# LED_Pannel.net
KiCad netlist of a schematic drawn in EAGLE
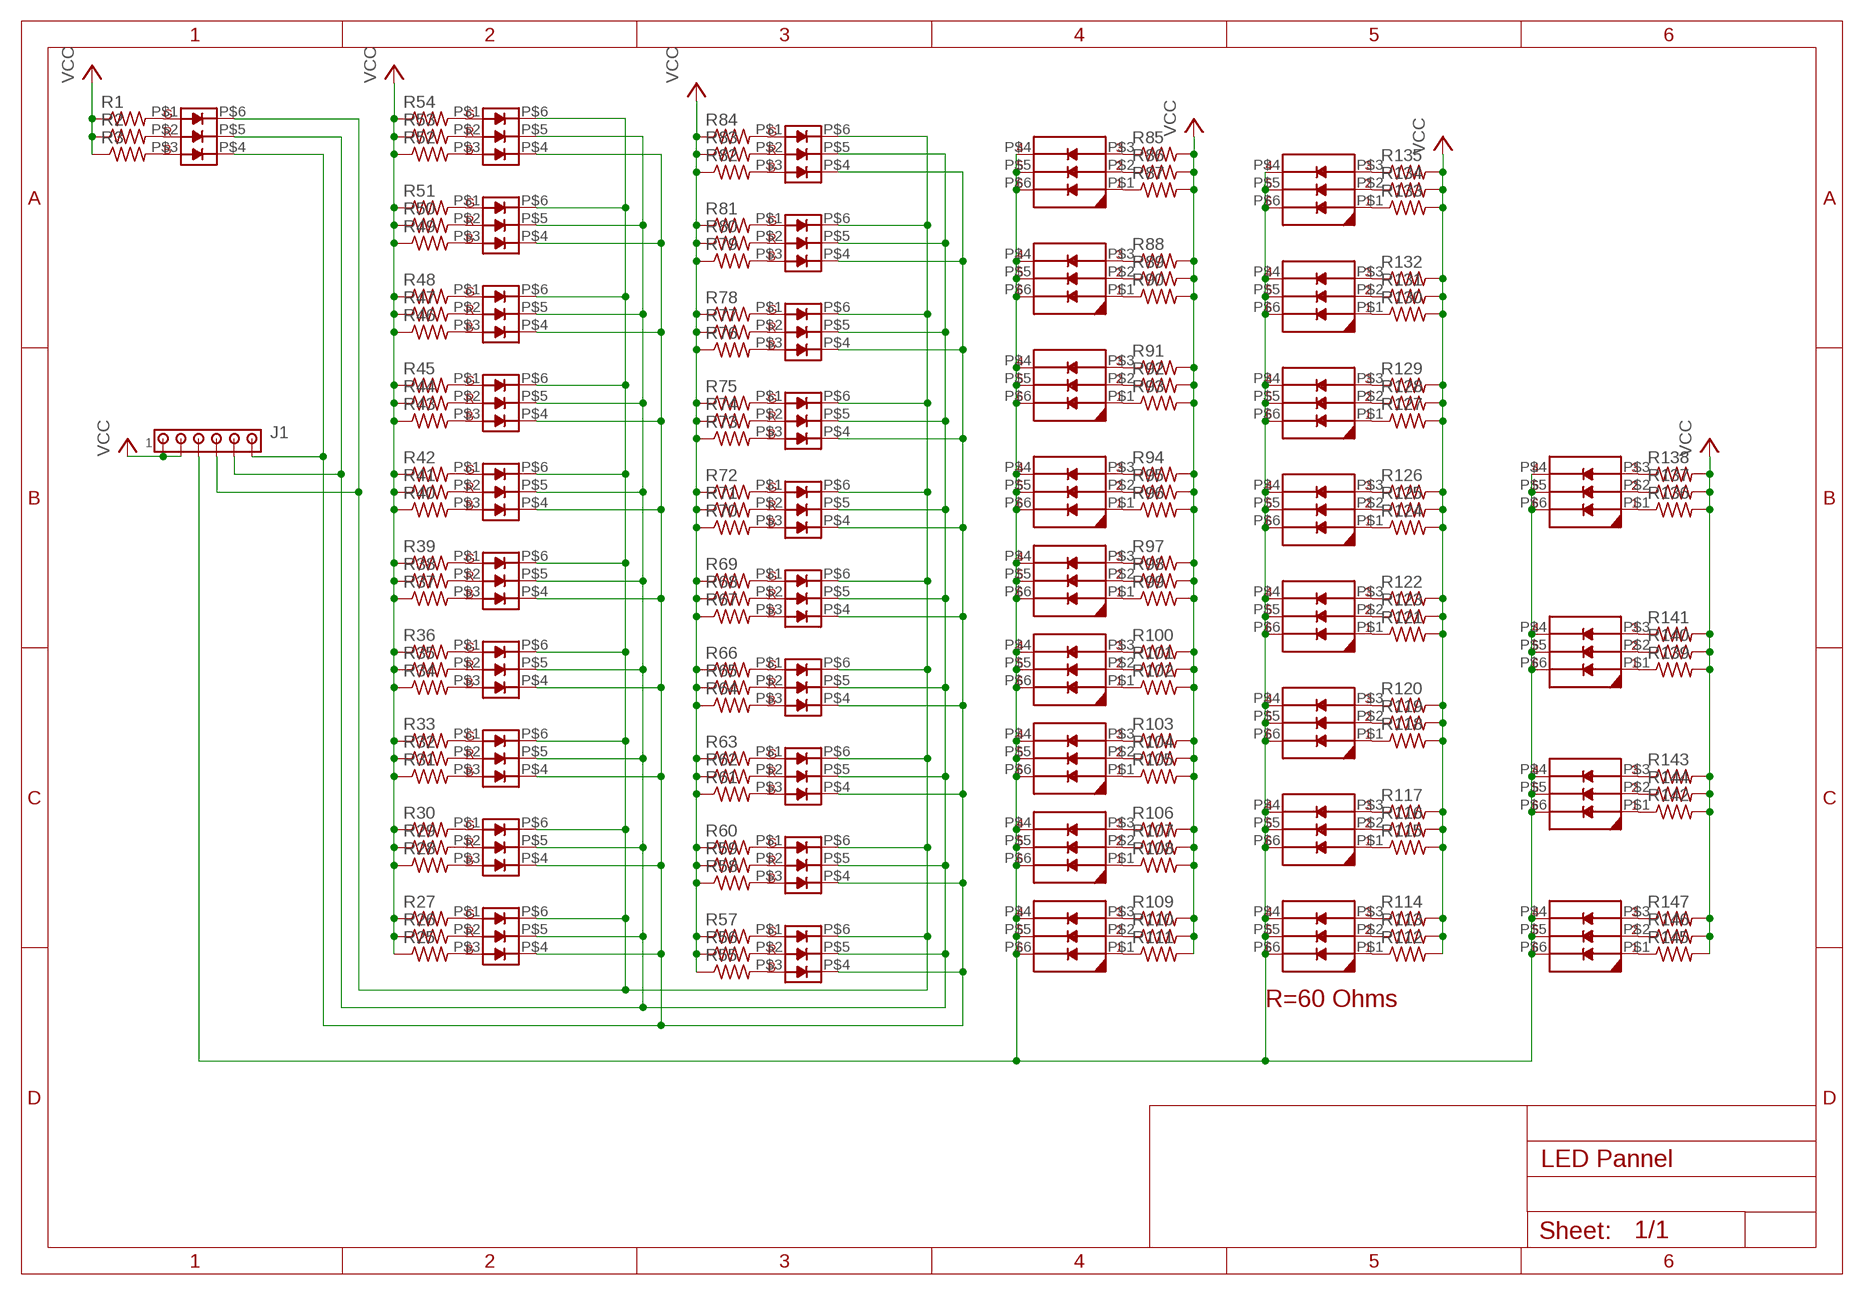
[diagram p0: schematic, sheet 1]

(export (version "E")
  (design (tool "Eeschema 10.0.6"))
  (components
    (comp (ref "J1")
      (value "MTA06-156")
      (footprint "eagle-import:1X6MTA")
      (libsource (lib "eagle-import") (part "MTA06-156"))
    )
    (comp (ref "R1")
      (value "R-US_R0603")
      (footprint "eagle-import:R0603")
      (libsource (lib "eagle-import") (part "R-US_R0603"))
    )
    (comp (ref "R2")
      (value "R-US_R0603")
      (footprint "eagle-import:R0603")
      (libsource (lib "eagle-import") (part "R-US_R0603"))
    )
    (comp (ref "R3")
      (value "R-US_R0603")
      (footprint "eagle-import:R0603")
      (libsource (lib "eagle-import") (part "R-US_R0603"))
    )
    (comp (ref "R25")
      (value "R-US_R0603")
      (footprint "eagle-import:R0603")
      (libsource (lib "eagle-import") (part "R-US_R0603"))
    )
    (comp (ref "R26")
      (value "R-US_R0603")
      (footprint "eagle-import:R0603")
      (libsource (lib "eagle-import") (part "R-US_R0603"))
    )
    (comp (ref "R27")
      (value "R-US_R0603")
      (footprint "eagle-import:R0603")
      (libsource (lib "eagle-import") (part "R-US_R0603"))
    )
    (comp (ref "R28")
      (value "R-US_R0603")
      (footprint "eagle-import:R0603")
      (libsource (lib "eagle-import") (part "R-US_R0603"))
    )
    (comp (ref "R29")
      (value "R-US_R0603")
      (footprint "eagle-import:R0603")
      (libsource (lib "eagle-import") (part "R-US_R0603"))
    )
    (comp (ref "R30")
      (value "R-US_R0603")
      (footprint "eagle-import:R0603")
      (libsource (lib "eagle-import") (part "R-US_R0603"))
    )
    (comp (ref "R31")
      (value "R-US_R0603")
      (footprint "eagle-import:R0603")
      (libsource (lib "eagle-import") (part "R-US_R0603"))
    )
    (comp (ref "R32")
      (value "R-US_R0603")
      (footprint "eagle-import:R0603")
      (libsource (lib "eagle-import") (part "R-US_R0603"))
    )
    (comp (ref "R33")
      (value "R-US_R0603")
      (footprint "eagle-import:R0603")
      (libsource (lib "eagle-import") (part "R-US_R0603"))
    )
    (comp (ref "R34")
      (value "R-US_R0603")
      (footprint "eagle-import:R0603")
      (libsource (lib "eagle-import") (part "R-US_R0603"))
    )
    (comp (ref "R35")
      (value "R-US_R0603")
      (footprint "eagle-import:R0603")
      (libsource (lib "eagle-import") (part "R-US_R0603"))
    )
    (comp (ref "R36")
      (value "R-US_R0603")
      (footprint "eagle-import:R0603")
      (libsource (lib "eagle-import") (part "R-US_R0603"))
    )
    (comp (ref "R37")
      (value "R-US_R0603")
      (footprint "eagle-import:R0603")
      (libsource (lib "eagle-import") (part "R-US_R0603"))
    )
    (comp (ref "R38")
      (value "R-US_R0603")
      (footprint "eagle-import:R0603")
      (libsource (lib "eagle-import") (part "R-US_R0603"))
    )
    (comp (ref "R39")
      (value "R-US_R0603")
      (footprint "eagle-import:R0603")
      (libsource (lib "eagle-import") (part "R-US_R0603"))
    )
    (comp (ref "R40")
      (value "R-US_R0603")
      (footprint "eagle-import:R0603")
      (libsource (lib "eagle-import") (part "R-US_R0603"))
    )
    (comp (ref "R41")
      (value "R-US_R0603")
      (footprint "eagle-import:R0603")
      (libsource (lib "eagle-import") (part "R-US_R0603"))
    )
    (comp (ref "R42")
      (value "R-US_R0603")
      (footprint "eagle-import:R0603")
      (libsource (lib "eagle-import") (part "R-US_R0603"))
    )
    (comp (ref "R43")
      (value "R-US_R0603")
      (footprint "eagle-import:R0603")
      (libsource (lib "eagle-import") (part "R-US_R0603"))
    )
    (comp (ref "R44")
      (value "R-US_R0603")
      (footprint "eagle-import:R0603")
      (libsource (lib "eagle-import") (part "R-US_R0603"))
    )
    (comp (ref "R45")
      (value "R-US_R0603")
      (footprint "eagle-import:R0603")
      (libsource (lib "eagle-import") (part "R-US_R0603"))
    )
    (comp (ref "R46")
      (value "R-US_R0603")
      (footprint "eagle-import:R0603")
      (libsource (lib "eagle-import") (part "R-US_R0603"))
    )
    (comp (ref "R47")
      (value "R-US_R0603")
      (footprint "eagle-import:R0603")
      (libsource (lib "eagle-import") (part "R-US_R0603"))
    )
    (comp (ref "R48")
      (value "R-US_R0603")
      (footprint "eagle-import:R0603")
      (libsource (lib "eagle-import") (part "R-US_R0603"))
    )
    (comp (ref "R49")
      (value "R-US_R0603")
      (footprint "eagle-import:R0603")
      (libsource (lib "eagle-import") (part "R-US_R0603"))
    )
    (comp (ref "R50")
      (value "R-US_R0603")
      (footprint "eagle-import:R0603")
      (libsource (lib "eagle-import") (part "R-US_R0603"))
    )
    (comp (ref "R51")
      (value "R-US_R0603")
      (footprint "eagle-import:R0603")
      (libsource (lib "eagle-import") (part "R-US_R0603"))
    )
    (comp (ref "R52")
      (value "R-US_R0603")
      (footprint "eagle-import:R0603")
      (libsource (lib "eagle-import") (part "R-US_R0603"))
    )
    (comp (ref "R53")
      (value "R-US_R0603")
      (footprint "eagle-import:R0603")
      (libsource (lib "eagle-import") (part "R-US_R0603"))
    )
    (comp (ref "R54")
      (value "R-US_R0603")
      (footprint "eagle-import:R0603")
      (libsource (lib "eagle-import") (part "R-US_R0603"))
    )
    (comp (ref "R55")
      (value "R-US_R0603")
      (footprint "eagle-import:R0603")
      (libsource (lib "eagle-import") (part "R-US_R0603"))
    )
    (comp (ref "R56")
      (value "R-US_R0603")
      (footprint "eagle-import:R0603")
      (libsource (lib "eagle-import") (part "R-US_R0603"))
    )
    (comp (ref "R57")
      (value "R-US_R0603")
      (footprint "eagle-import:R0603")
      (libsource (lib "eagle-import") (part "R-US_R0603"))
    )
    (comp (ref "R58")
      (value "R-US_R0603")
      (footprint "eagle-import:R0603")
      (libsource (lib "eagle-import") (part "R-US_R0603"))
    )
    (comp (ref "R59")
      (value "R-US_R0603")
      (footprint "eagle-import:R0603")
      (libsource (lib "eagle-import") (part "R-US_R0603"))
    )
    (comp (ref "R60")
      (value "R-US_R0603")
      (footprint "eagle-import:R0603")
      (libsource (lib "eagle-import") (part "R-US_R0603"))
    )
    (comp (ref "R61")
      (value "R-US_R0603")
      (footprint "eagle-import:R0603")
      (libsource (lib "eagle-import") (part "R-US_R0603"))
    )
    (comp (ref "R62")
      (value "R-US_R0603")
      (footprint "eagle-import:R0603")
      (libsource (lib "eagle-import") (part "R-US_R0603"))
    )
    (comp (ref "R63")
      (value "R-US_R0603")
      (footprint "eagle-import:R0603")
      (libsource (lib "eagle-import") (part "R-US_R0603"))
    )
    (comp (ref "R64")
      (value "R-US_R0603")
      (footprint "eagle-import:R0603")
      (libsource (lib "eagle-import") (part "R-US_R0603"))
    )
    (comp (ref "R65")
      (value "R-US_R0603")
      (footprint "eagle-import:R0603")
      (libsource (lib "eagle-import") (part "R-US_R0603"))
    )
    (comp (ref "R66")
      (value "R-US_R0603")
      (footprint "eagle-import:R0603")
      (libsource (lib "eagle-import") (part "R-US_R0603"))
    )
    (comp (ref "R67")
      (value "R-US_R0603")
      (footprint "eagle-import:R0603")
      (libsource (lib "eagle-import") (part "R-US_R0603"))
    )
    (comp (ref "R68")
      (value "R-US_R0603")
      (footprint "eagle-import:R0603")
      (libsource (lib "eagle-import") (part "R-US_R0603"))
    )
    (comp (ref "R69")
      (value "R-US_R0603")
      (footprint "eagle-import:R0603")
      (libsource (lib "eagle-import") (part "R-US_R0603"))
    )
    (comp (ref "R70")
      (value "R-US_R0603")
      (footprint "eagle-import:R0603")
      (libsource (lib "eagle-import") (part "R-US_R0603"))
    )
    (comp (ref "R71")
      (value "R-US_R0603")
      (footprint "eagle-import:R0603")
      (libsource (lib "eagle-import") (part "R-US_R0603"))
    )
    (comp (ref "R72")
      (value "R-US_R0603")
      (footprint "eagle-import:R0603")
      (libsource (lib "eagle-import") (part "R-US_R0603"))
    )
    (comp (ref "R73")
      (value "R-US_R0603")
      (footprint "eagle-import:R0603")
      (libsource (lib "eagle-import") (part "R-US_R0603"))
    )
    (comp (ref "R74")
      (value "R-US_R0603")
      (footprint "eagle-import:R0603")
      (libsource (lib "eagle-import") (part "R-US_R0603"))
    )
    (comp (ref "R75")
      (value "R-US_R0603")
      (footprint "eagle-import:R0603")
      (libsource (lib "eagle-import") (part "R-US_R0603"))
    )
    (comp (ref "R76")
      (value "R-US_R0603")
      (footprint "eagle-import:R0603")
      (libsource (lib "eagle-import") (part "R-US_R0603"))
    )
    (comp (ref "R77")
      (value "R-US_R0603")
      (footprint "eagle-import:R0603")
      (libsource (lib "eagle-import") (part "R-US_R0603"))
    )
    (comp (ref "R78")
      (value "R-US_R0603")
      (footprint "eagle-import:R0603")
      (libsource (lib "eagle-import") (part "R-US_R0603"))
    )
    (comp (ref "R79")
      (value "R-US_R0603")
      (footprint "eagle-import:R0603")
      (libsource (lib "eagle-import") (part "R-US_R0603"))
    )
    (comp (ref "R80")
      (value "R-US_R0603")
      (footprint "eagle-import:R0603")
      (libsource (lib "eagle-import") (part "R-US_R0603"))
    )
    (comp (ref "R81")
      (value "R-US_R0603")
      (footprint "eagle-import:R0603")
      (libsource (lib "eagle-import") (part "R-US_R0603"))
    )
    (comp (ref "R82")
      (value "R-US_R0603")
      (footprint "eagle-import:R0603")
      (libsource (lib "eagle-import") (part "R-US_R0603"))
    )
    (comp (ref "R83")
      (value "R-US_R0603")
      (footprint "eagle-import:R0603")
      (libsource (lib "eagle-import") (part "R-US_R0603"))
    )
    (comp (ref "R84")
      (value "R-US_R0603")
      (footprint "eagle-import:R0603")
      (libsource (lib "eagle-import") (part "R-US_R0603"))
    )
    (comp (ref "R85")
      (value "R-US_R0603")
      (footprint "eagle-import:R0603")
      (libsource (lib "eagle-import") (part "R-US_R0603"))
    )
    (comp (ref "R86")
      (value "R-US_R0603")
      (footprint "eagle-import:R0603")
      (libsource (lib "eagle-import") (part "R-US_R0603"))
    )
    (comp (ref "R87")
      (value "R-US_R0603")
      (footprint "eagle-import:R0603")
      (libsource (lib "eagle-import") (part "R-US_R0603"))
    )
    (comp (ref "R88")
      (value "R-US_R0603")
      (footprint "eagle-import:R0603")
      (libsource (lib "eagle-import") (part "R-US_R0603"))
    )
    (comp (ref "R89")
      (value "R-US_R0603")
      (footprint "eagle-import:R0603")
      (libsource (lib "eagle-import") (part "R-US_R0603"))
    )
    (comp (ref "R90")
      (value "R-US_R0603")
      (footprint "eagle-import:R0603")
      (libsource (lib "eagle-import") (part "R-US_R0603"))
    )
    (comp (ref "R91")
      (value "R-US_R0603")
      (footprint "eagle-import:R0603")
      (libsource (lib "eagle-import") (part "R-US_R0603"))
    )
    (comp (ref "R92")
      (value "R-US_R0603")
      (footprint "eagle-import:R0603")
      (libsource (lib "eagle-import") (part "R-US_R0603"))
    )
    (comp (ref "R93")
      (value "R-US_R0603")
      (footprint "eagle-import:R0603")
      (libsource (lib "eagle-import") (part "R-US_R0603"))
    )
    (comp (ref "R94")
      (value "R-US_R0603")
      (footprint "eagle-import:R0603")
      (libsource (lib "eagle-import") (part "R-US_R0603"))
    )
    (comp (ref "R95")
      (value "R-US_R0603")
      (footprint "eagle-import:R0603")
      (libsource (lib "eagle-import") (part "R-US_R0603"))
    )
    (comp (ref "R96")
      (value "R-US_R0603")
      (footprint "eagle-import:R0603")
      (libsource (lib "eagle-import") (part "R-US_R0603"))
    )
    (comp (ref "R97")
      (value "R-US_R0603")
      (footprint "eagle-import:R0603")
      (libsource (lib "eagle-import") (part "R-US_R0603"))
    )
    (comp (ref "R98")
      (value "R-US_R0603")
      (footprint "eagle-import:R0603")
      (libsource (lib "eagle-import") (part "R-US_R0603"))
    )
    (comp (ref "R99")
      (value "R-US_R0603")
      (footprint "eagle-import:R0603")
      (libsource (lib "eagle-import") (part "R-US_R0603"))
    )
    (comp (ref "R100")
      (value "R-US_R0603")
      (footprint "eagle-import:R0603")
      (libsource (lib "eagle-import") (part "R-US_R0603"))
    )
    (comp (ref "R101")
      (value "R-US_R0603")
      (footprint "eagle-import:R0603")
      (libsource (lib "eagle-import") (part "R-US_R0603"))
    )
    (comp (ref "R102")
      (value "R-US_R0603")
      (footprint "eagle-import:R0603")
      (libsource (lib "eagle-import") (part "R-US_R0603"))
    )
    (comp (ref "R103")
      (value "R-US_R0603")
      (footprint "eagle-import:R0603")
      (libsource (lib "eagle-import") (part "R-US_R0603"))
    )
    (comp (ref "R104")
      (value "R-US_R0603")
      (footprint "eagle-import:R0603")
      (libsource (lib "eagle-import") (part "R-US_R0603"))
    )
    (comp (ref "R105")
      (value "R-US_R0603")
      (footprint "eagle-import:R0603")
      (libsource (lib "eagle-import") (part "R-US_R0603"))
    )
    (comp (ref "R106")
      (value "R-US_R0603")
      (footprint "eagle-import:R0603")
      (libsource (lib "eagle-import") (part "R-US_R0603"))
    )
    (comp (ref "R107")
      (value "R-US_R0603")
      (footprint "eagle-import:R0603")
      (libsource (lib "eagle-import") (part "R-US_R0603"))
    )
    (comp (ref "R108")
      (value "R-US_R0603")
      (footprint "eagle-import:R0603")
      (libsource (lib "eagle-import") (part "R-US_R0603"))
    )
    (comp (ref "R109")
      (value "R-US_R0603")
      (footprint "eagle-import:R0603")
      (libsource (lib "eagle-import") (part "R-US_R0603"))
    )
    (comp (ref "R110")
      (value "R-US_R0603")
      (footprint "eagle-import:R0603")
      (libsource (lib "eagle-import") (part "R-US_R0603"))
    )
    (comp (ref "R111")
      (value "R-US_R0603")
      (footprint "eagle-import:R0603")
      (libsource (lib "eagle-import") (part "R-US_R0603"))
    )
    (comp (ref "R112")
      (value "R-US_R0603")
      (footprint "eagle-import:R0603")
      (libsource (lib "eagle-import") (part "R-US_R0603"))
    )
    (comp (ref "R113")
      (value "R-US_R0603")
      (footprint "eagle-import:R0603")
      (libsource (lib "eagle-import") (part "R-US_R0603"))
    )
    (comp (ref "R114")
      (value "R-US_R0603")
      (footprint "eagle-import:R0603")
      (libsource (lib "eagle-import") (part "R-US_R0603"))
    )
    (comp (ref "R115")
      (value "R-US_R0603")
      (footprint "eagle-import:R0603")
      (libsource (lib "eagle-import") (part "R-US_R0603"))
    )
    (comp (ref "R116")
      (value "R-US_R0603")
      (footprint "eagle-import:R0603")
      (libsource (lib "eagle-import") (part "R-US_R0603"))
    )
    (comp (ref "R117")
      (value "R-US_R0603")
      (footprint "eagle-import:R0603")
      (libsource (lib "eagle-import") (part "R-US_R0603"))
    )
    (comp (ref "R118")
      (value "R-US_R0603")
      (footprint "eagle-import:R0603")
      (libsource (lib "eagle-import") (part "R-US_R0603"))
    )
    (comp (ref "R119")
      (value "R-US_R0603")
      (footprint "eagle-import:R0603")
      (libsource (lib "eagle-import") (part "R-US_R0603"))
    )
    (comp (ref "R120")
      (value "R-US_R0603")
      (footprint "eagle-import:R0603")
      (libsource (lib "eagle-import") (part "R-US_R0603"))
    )
    (comp (ref "R121")
      (value "R-US_R0603")
      (footprint "eagle-import:R0603")
      (libsource (lib "eagle-import") (part "R-US_R0603"))
    )
    (comp (ref "R122")
      (value "R-US_R0603")
      (footprint "eagle-import:R0603")
      (libsource (lib "eagle-import") (part "R-US_R0603"))
    )
    (comp (ref "R123")
      (value "R-US_R0603")
      (footprint "eagle-import:R0603")
      (libsource (lib "eagle-import") (part "R-US_R0603"))
    )
    (comp (ref "R124")
      (value "R-US_R0603")
      (footprint "eagle-import:R0603")
      (libsource (lib "eagle-import") (part "R-US_R0603"))
    )
    (comp (ref "R125")
      (value "R-US_R0603")
      (footprint "eagle-import:R0603")
      (libsource (lib "eagle-import") (part "R-US_R0603"))
    )
    (comp (ref "R126")
      (value "R-US_R0603")
      (footprint "eagle-import:R0603")
      (libsource (lib "eagle-import") (part "R-US_R0603"))
    )
    (comp (ref "R127")
      (value "R-US_R0603")
      (footprint "eagle-import:R0603")
      (libsource (lib "eagle-import") (part "R-US_R0603"))
    )
    (comp (ref "R128")
      (value "R-US_R0603")
      (footprint "eagle-import:R0603")
      (libsource (lib "eagle-import") (part "R-US_R0603"))
    )
    (comp (ref "R129")
      (value "R-US_R0603")
      (footprint "eagle-import:R0603")
      (libsource (lib "eagle-import") (part "R-US_R0603"))
    )
    (comp (ref "R130")
      (value "R-US_R0603")
      (footprint "eagle-import:R0603")
      (libsource (lib "eagle-import") (part "R-US_R0603"))
    )
    (comp (ref "R131")
      (value "R-US_R0603")
      (footprint "eagle-import:R0603")
      (libsource (lib "eagle-import") (part "R-US_R0603"))
    )
    (comp (ref "R132")
      (value "R-US_R0603")
      (footprint "eagle-import:R0603")
      (libsource (lib "eagle-import") (part "R-US_R0603"))
    )
    (comp (ref "R133")
      (value "R-US_R0603")
      (footprint "eagle-import:R0603")
      (libsource (lib "eagle-import") (part "R-US_R0603"))
    )
    (comp (ref "R134")
      (value "R-US_R0603")
      (footprint "eagle-import:R0603")
      (libsource (lib "eagle-import") (part "R-US_R0603"))
    )
    (comp (ref "R135")
      (value "R-US_R0603")
      (footprint "eagle-import:R0603")
      (libsource (lib "eagle-import") (part "R-US_R0603"))
    )
    (comp (ref "R136")
      (value "R-US_R0603")
      (footprint "eagle-import:R0603")
      (libsource (lib "eagle-import") (part "R-US_R0603"))
    )
    (comp (ref "R137")
      (value "R-US_R0603")
      (footprint "eagle-import:R0603")
      (libsource (lib "eagle-import") (part "R-US_R0603"))
    )
    (comp (ref "R138")
      (value "R-US_R0603")
      (footprint "eagle-import:R0603")
      (libsource (lib "eagle-import") (part "R-US_R0603"))
    )
    (comp (ref "R139")
      (value "R-US_R0603")
      (footprint "eagle-import:R0603")
      (libsource (lib "eagle-import") (part "R-US_R0603"))
    )
    (comp (ref "R140")
      (value "R-US_R0603")
      (footprint "eagle-import:R0603")
      (libsource (lib "eagle-import") (part "R-US_R0603"))
    )
    (comp (ref "R141")
      (value "R-US_R0603")
      (footprint "eagle-import:R0603")
      (libsource (lib "eagle-import") (part "R-US_R0603"))
    )
    (comp (ref "R142")
      (value "R-US_R0603")
      (footprint "eagle-import:R0603")
      (libsource (lib "eagle-import") (part "R-US_R0603"))
    )
    (comp (ref "R143")
      (value "R-US_R0603")
      (footprint "eagle-import:R0603")
      (libsource (lib "eagle-import") (part "R-US_R0603"))
    )
    (comp (ref "R144")
      (value "R-US_R0603")
      (footprint "eagle-import:R0603")
      (libsource (lib "eagle-import") (part "R-US_R0603"))
    )
    (comp (ref "R145")
      (value "R-US_R0603")
      (footprint "eagle-import:R0603")
      (libsource (lib "eagle-import") (part "R-US_R0603"))
    )
    (comp (ref "R146")
      (value "R-US_R0603")
      (footprint "eagle-import:R0603")
      (libsource (lib "eagle-import") (part "R-US_R0603"))
    )
    (comp (ref "R147")
      (value "R-US_R0603")
      (footprint "eagle-import:R0603")
      (libsource (lib "eagle-import") (part "R-US_R0603"))
    )
    (comp (ref "U$1")
      (value "RGB_LED")
      (footprint "eagle-import:5050")
      (libsource (lib "eagle-import") (part "RGB_LED"))
    )
    (comp (ref "U$2")
      (value "RGB_LED")
      (footprint "eagle-import:5050")
      (libsource (lib "eagle-import") (part "RGB_LED"))
    )
    (comp (ref "U$3")
      (value "RGB_LED")
      (footprint "eagle-import:5050")
      (libsource (lib "eagle-import") (part "RGB_LED"))
    )
    (comp (ref "U$4")
      (value "RGB_LED")
      (footprint "eagle-import:5050")
      (libsource (lib "eagle-import") (part "RGB_LED"))
    )
    (comp (ref "U$5")
      (value "RGB_LED")
      (footprint "eagle-import:5050")
      (libsource (lib "eagle-import") (part "RGB_LED"))
    )
    (comp (ref "U$6")
      (value "RGB_LED")
      (footprint "eagle-import:5050")
      (libsource (lib "eagle-import") (part "RGB_LED"))
    )
    (comp (ref "U$7")
      (value "RGB_LED")
      (footprint "eagle-import:5050")
      (libsource (lib "eagle-import") (part "RGB_LED"))
    )
    (comp (ref "U$8")
      (value "RGB_LED")
      (footprint "eagle-import:5050")
      (libsource (lib "eagle-import") (part "RGB_LED"))
    )
    (comp (ref "U$9")
      (value "RGB_LED")
      (footprint "eagle-import:5050")
      (libsource (lib "eagle-import") (part "RGB_LED"))
    )
    (comp (ref "U$10")
      (value "RGB_LED")
      (footprint "eagle-import:5050")
      (libsource (lib "eagle-import") (part "RGB_LED"))
    )
    (comp (ref "U$11")
      (value "WHITE_LED")
      (footprint "eagle-import:5050")
      (libsource (lib "eagle-import") (part "WHITE_LED"))
    )
    (comp (ref "U$12")
      (value "WHITE_LED")
      (footprint "eagle-import:5050")
      (libsource (lib "eagle-import") (part "WHITE_LED"))
    )
    (comp (ref "U$13")
      (value "WHITE_LED")
      (footprint "eagle-import:5050")
      (libsource (lib "eagle-import") (part "WHITE_LED"))
    )
    (comp (ref "U$14")
      (value "WHITE_LED")
      (footprint "eagle-import:5050")
      (libsource (lib "eagle-import") (part "WHITE_LED"))
    )
    (comp (ref "U$15")
      (value "WHITE_LED")
      (footprint "eagle-import:5050")
      (libsource (lib "eagle-import") (part "WHITE_LED"))
    )
    (comp (ref "U$16")
      (value "WHITE_LED")
      (footprint "eagle-import:5050")
      (libsource (lib "eagle-import") (part "WHITE_LED"))
    )
    (comp (ref "U$17")
      (value "RGB_LED")
      (footprint "eagle-import:5050")
      (libsource (lib "eagle-import") (part "RGB_LED"))
    )
    (comp (ref "U$18")
      (value "RGB_LED")
      (footprint "eagle-import:5050")
      (libsource (lib "eagle-import") (part "RGB_LED"))
    )
    (comp (ref "U$19")
      (value "RGB_LED")
      (footprint "eagle-import:5050")
      (libsource (lib "eagle-import") (part "RGB_LED"))
    )
    (comp (ref "U$20")
      (value "RGB_LED")
      (footprint "eagle-import:5050")
      (libsource (lib "eagle-import") (part "RGB_LED"))
    )
    (comp (ref "U$21")
      (value "RGB_LED")
      (footprint "eagle-import:5050")
      (libsource (lib "eagle-import") (part "RGB_LED"))
    )
    (comp (ref "U$22")
      (value "RGB_LED")
      (footprint "eagle-import:5050")
      (libsource (lib "eagle-import") (part "RGB_LED"))
    )
    (comp (ref "U$23")
      (value "RGB_LED")
      (footprint "eagle-import:5050")
      (libsource (lib "eagle-import") (part "RGB_LED"))
    )
    (comp (ref "U$24")
      (value "RGB_LED")
      (footprint "eagle-import:5050")
      (libsource (lib "eagle-import") (part "RGB_LED"))
    )
    (comp (ref "U$25")
      (value "RGB_LED")
      (footprint "eagle-import:5050")
      (libsource (lib "eagle-import") (part "RGB_LED"))
    )
    (comp (ref "U$26")
      (value "RGB_LED")
      (footprint "eagle-import:5050")
      (libsource (lib "eagle-import") (part "RGB_LED"))
    )
    (comp (ref "U$27")
      (value "RGB_LED")
      (footprint "eagle-import:5050")
      (libsource (lib "eagle-import") (part "RGB_LED"))
    )
    (comp (ref "U$35")
      (value "WHITE_LED")
      (footprint "eagle-import:5050")
      (libsource (lib "eagle-import") (part "WHITE_LED"))
    )
    (comp (ref "U$36")
      (value "WHITE_LED")
      (footprint "eagle-import:5050")
      (libsource (lib "eagle-import") (part "WHITE_LED"))
    )
    (comp (ref "U$37")
      (value "WHITE_LED")
      (footprint "eagle-import:5050")
      (libsource (lib "eagle-import") (part "WHITE_LED"))
    )
    (comp (ref "U$38")
      (value "WHITE_LED")
      (footprint "eagle-import:5050")
      (libsource (lib "eagle-import") (part "WHITE_LED"))
    )
    (comp (ref "U$47")
      (value "WHITE_LED")
      (footprint "eagle-import:5050")
      (libsource (lib "eagle-import") (part "WHITE_LED"))
    )
    (comp (ref "U$48")
      (value "WHITE_LED")
      (footprint "eagle-import:5050")
      (libsource (lib "eagle-import") (part "WHITE_LED"))
    )
    (comp (ref "U$49")
      (value "WHITE_LED")
      (footprint "eagle-import:5050")
      (libsource (lib "eagle-import") (part "WHITE_LED"))
    )
    (comp (ref "U$50")
      (value "WHITE_LED")
      (footprint "eagle-import:5050")
      (libsource (lib "eagle-import") (part "WHITE_LED"))
    )
    (comp (ref "U$51")
      (value "WHITE_LED")
      (footprint "eagle-import:5050")
      (libsource (lib "eagle-import") (part "WHITE_LED"))
    )
    (comp (ref "U$52")
      (value "WHITE_LED")
      (footprint "eagle-import:5050")
      (libsource (lib "eagle-import") (part "WHITE_LED"))
    )
    (comp (ref "U$53")
      (value "WHITE_LED")
      (footprint "eagle-import:5050")
      (libsource (lib "eagle-import") (part "WHITE_LED"))
    )
    (comp (ref "U$54")
      (value "WHITE_LED")
      (footprint "eagle-import:5050")
      (libsource (lib "eagle-import") (part "WHITE_LED"))
    )
    (comp (ref "U$55")
      (value "WHITE_LED")
      (footprint "eagle-import:5050")
      (libsource (lib "eagle-import") (part "WHITE_LED"))
    )
    (comp (ref "U$56")
      (value "WHITE_LED")
      (footprint "eagle-import:5050")
      (libsource (lib "eagle-import") (part "WHITE_LED"))
    )
    (comp (ref "U$57")
      (value "WHITE_LED")
      (footprint "eagle-import:5050")
      (libsource (lib "eagle-import") (part "WHITE_LED"))
    )
  )
  (nets
    (net (code "1") (name "Net-(J1-Pad3)") (class "Default")
      (node (ref "J1") (pin "3") (pinfunction "3_3") (pintype "passive"))
      (node (ref "U$11") (pin "P$4") (pinfunction "P$4_P$4") (pintype "bidirectional"))
      (node (ref "U$11") (pin "P$5") (pinfunction "P$5_P$5") (pintype "bidirectional"))
      (node (ref "U$11") (pin "P$6") (pinfunction "P$6_P$6") (pintype "bidirectional"))
      (node (ref "U$12") (pin "P$4") (pinfunction "P$4_P$4") (pintype "bidirectional"))
      (node (ref "U$12") (pin "P$5") (pinfunction "P$5_P$5") (pintype "bidirectional"))
      (node (ref "U$12") (pin "P$6") (pinfunction "P$6_P$6") (pintype "bidirectional"))
      (node (ref "U$13") (pin "P$4") (pinfunction "P$4_P$4") (pintype "bidirectional"))
      (node (ref "U$13") (pin "P$5") (pinfunction "P$5_P$5") (pintype "bidirectional"))
      (node (ref "U$13") (pin "P$6") (pinfunction "P$6_P$6") (pintype "bidirectional"))
      (node (ref "U$14") (pin "P$4") (pinfunction "P$4_P$4") (pintype "bidirectional"))
      (node (ref "U$14") (pin "P$5") (pinfunction "P$5_P$5") (pintype "bidirectional"))
      (node (ref "U$14") (pin "P$6") (pinfunction "P$6_P$6") (pintype "bidirectional"))
      (node (ref "U$15") (pin "P$4") (pinfunction "P$4_P$4") (pintype "bidirectional"))
      (node (ref "U$15") (pin "P$5") (pinfunction "P$5_P$5") (pintype "bidirectional"))
      (node (ref "U$15") (pin "P$6") (pinfunction "P$6_P$6") (pintype "bidirectional"))
      (node (ref "U$16") (pin "P$4") (pinfunction "P$4_P$4") (pintype "bidirectional"))
      (node (ref "U$16") (pin "P$5") (pinfunction "P$5_P$5") (pintype "bidirectional"))
      (node (ref "U$16") (pin "P$6") (pinfunction "P$6_P$6") (pintype "bidirectional"))
      (node (ref "U$35") (pin "P$4") (pinfunction "P$4_P$4") (pintype "bidirectional"))
      (node (ref "U$35") (pin "P$5") (pinfunction "P$5_P$5") (pintype "bidirectional"))
      (node (ref "U$35") (pin "P$6") (pinfunction "P$6_P$6") (pintype "bidirectional"))
      (node (ref "U$36") (pin "P$4") (pinfunction "P$4_P$4") (pintype "bidirectional"))
      (node (ref "U$36") (pin "P$5") (pinfunction "P$5_P$5") (pintype "bidirectional"))
      (node (ref "U$36") (pin "P$6") (pinfunction "P$6_P$6") (pintype "bidirectional"))
      (node (ref "U$37") (pin "P$4") (pinfunction "P$4_P$4") (pintype "bidirectional"))
      (node (ref "U$37") (pin "P$5") (pinfunction "P$5_P$5") (pintype "bidirectional"))
      (node (ref "U$37") (pin "P$6") (pinfunction "P$6_P$6") (pintype "bidirectional"))
      (node (ref "U$38") (pin "P$4") (pinfunction "P$4_P$4") (pintype "bidirectional"))
      (node (ref "U$38") (pin "P$5") (pinfunction "P$5_P$5") (pintype "bidirectional"))
      (node (ref "U$38") (pin "P$6") (pinfunction "P$6_P$6") (pintype "bidirectional"))
      (node (ref "U$47") (pin "P$4") (pinfunction "P$4_P$4") (pintype "bidirectional"))
      (node (ref "U$47") (pin "P$5") (pinfunction "P$5_P$5") (pintype "bidirectional"))
      (node (ref "U$47") (pin "P$6") (pinfunction "P$6_P$6") (pintype "bidirectional"))
      (node (ref "U$48") (pin "P$4") (pinfunction "P$4_P$4") (pintype "bidirectional"))
      (node (ref "U$48") (pin "P$5") (pinfunction "P$5_P$5") (pintype "bidirectional"))
      (node (ref "U$48") (pin "P$6") (pinfunction "P$6_P$6") (pintype "bidirectional"))
      (node (ref "U$49") (pin "P$4") (pinfunction "P$4_P$4") (pintype "bidirectional"))
      (node (ref "U$49") (pin "P$5") (pinfunction "P$5_P$5") (pintype "bidirectional"))
      (node (ref "U$49") (pin "P$6") (pinfunction "P$6_P$6") (pintype "bidirectional"))
      (node (ref "U$50") (pin "P$4") (pinfunction "P$4_P$4") (pintype "bidirectional"))
      (node (ref "U$50") (pin "P$5") (pinfunction "P$5_P$5") (pintype "bidirectional"))
      (node (ref "U$50") (pin "P$6") (pinfunction "P$6_P$6") (pintype "bidirectional"))
      (node (ref "U$51") (pin "P$4") (pinfunction "P$4_P$4") (pintype "bidirectional"))
      (node (ref "U$51") (pin "P$5") (pinfunction "P$5_P$5") (pintype "bidirectional"))
      (node (ref "U$51") (pin "P$6") (pinfunction "P$6_P$6") (pintype "bidirectional"))
      (node (ref "U$52") (pin "P$4") (pinfunction "P$4_P$4") (pintype "bidirectional"))
      (node (ref "U$52") (pin "P$5") (pinfunction "P$5_P$5") (pintype "bidirectional"))
      (node (ref "U$52") (pin "P$6") (pinfunction "P$6_P$6") (pintype "bidirectional"))
      (node (ref "U$53") (pin "P$4") (pinfunction "P$4_P$4") (pintype "bidirectional"))
      (node (ref "U$53") (pin "P$5") (pinfunction "P$5_P$5") (pintype "bidirectional"))
      (node (ref "U$53") (pin "P$6") (pinfunction "P$6_P$6") (pintype "bidirectional"))
      (node (ref "U$54") (pin "P$4") (pinfunction "P$4_P$4") (pintype "bidirectional"))
      (node (ref "U$54") (pin "P$5") (pinfunction "P$5_P$5") (pintype "bidirectional"))
      (node (ref "U$54") (pin "P$6") (pinfunction "P$6_P$6") (pintype "bidirectional"))
      (node (ref "U$55") (pin "P$4") (pinfunction "P$4_P$4") (pintype "bidirectional"))
      (node (ref "U$55") (pin "P$5") (pinfunction "P$5_P$5") (pintype "bidirectional"))
      (node (ref "U$55") (pin "P$6") (pinfunction "P$6_P$6") (pintype "bidirectional"))
      (node (ref "U$56") (pin "P$4") (pinfunction "P$4_P$4") (pintype "bidirectional"))
      (node (ref "U$56") (pin "P$5") (pinfunction "P$5_P$5") (pintype "bidirectional"))
      (node (ref "U$56") (pin "P$6") (pinfunction "P$6_P$6") (pintype "bidirectional"))
      (node (ref "U$57") (pin "P$4") (pinfunction "P$4_P$4") (pintype "bidirectional"))
      (node (ref "U$57") (pin "P$5") (pinfunction "P$5_P$5") (pintype "bidirectional"))
      (node (ref "U$57") (pin "P$6") (pinfunction "P$6_P$6") (pintype "bidirectional"))
    )
    (net (code "2") (name "Net-(J1-Pad4)") (class "Default")
      (node (ref "J1") (pin "4") (pinfunction "4_4") (pintype "passive"))
      (node (ref "U$1") (pin "P$6") (pinfunction "P$6_P$6") (pintype "bidirectional"))
      (node (ref "U$10") (pin "P$6") (pinfunction "P$6_P$6") (pintype "bidirectional"))
      (node (ref "U$17") (pin "P$6") (pinfunction "P$6_P$6") (pintype "bidirectional"))
      (node (ref "U$18") (pin "P$6") (pinfunction "P$6_P$6") (pintype "bidirectional"))
      (node (ref "U$19") (pin "P$6") (pinfunction "P$6_P$6") (pintype "bidirectional"))
      (node (ref "U$2") (pin "P$6") (pinfunction "P$6_P$6") (pintype "bidirectional"))
      (node (ref "U$20") (pin "P$6") (pinfunction "P$6_P$6") (pintype "bidirectional"))
      (node (ref "U$21") (pin "P$6") (pinfunction "P$6_P$6") (pintype "bidirectional"))
      (node (ref "U$22") (pin "P$6") (pinfunction "P$6_P$6") (pintype "bidirectional"))
      (node (ref "U$23") (pin "P$6") (pinfunction "P$6_P$6") (pintype "bidirectional"))
      (node (ref "U$24") (pin "P$6") (pinfunction "P$6_P$6") (pintype "bidirectional"))
      (node (ref "U$25") (pin "P$6") (pinfunction "P$6_P$6") (pintype "bidirectional"))
      (node (ref "U$26") (pin "P$6") (pinfunction "P$6_P$6") (pintype "bidirectional"))
      (node (ref "U$27") (pin "P$6") (pinfunction "P$6_P$6") (pintype "bidirectional"))
      (node (ref "U$3") (pin "P$6") (pinfunction "P$6_P$6") (pintype "bidirectional"))
      (node (ref "U$4") (pin "P$6") (pinfunction "P$6_P$6") (pintype "bidirectional"))
      (node (ref "U$5") (pin "P$6") (pinfunction "P$6_P$6") (pintype "bidirectional"))
      (node (ref "U$6") (pin "P$6") (pinfunction "P$6_P$6") (pintype "bidirectional"))
      (node (ref "U$7") (pin "P$6") (pinfunction "P$6_P$6") (pintype "bidirectional"))
      (node (ref "U$8") (pin "P$6") (pinfunction "P$6_P$6") (pintype "bidirectional"))
      (node (ref "U$9") (pin "P$6") (pinfunction "P$6_P$6") (pintype "bidirectional"))
    )
    (net (code "3") (name "Net-(J1-Pad5)") (class "Default")
      (node (ref "J1") (pin "5") (pinfunction "5_5") (pintype "passive"))
      (node (ref "U$1") (pin "P$5") (pinfunction "P$5_P$5") (pintype "bidirectional"))
      (node (ref "U$10") (pin "P$5") (pinfunction "P$5_P$5") (pintype "bidirectional"))
      (node (ref "U$17") (pin "P$5") (pinfunction "P$5_P$5") (pintype "bidirectional"))
      (node (ref "U$18") (pin "P$5") (pinfunction "P$5_P$5") (pintype "bidirectional"))
      (node (ref "U$19") (pin "P$5") (pinfunction "P$5_P$5") (pintype "bidirectional"))
      (node (ref "U$2") (pin "P$5") (pinfunction "P$5_P$5") (pintype "bidirectional"))
      (node (ref "U$20") (pin "P$5") (pinfunction "P$5_P$5") (pintype "bidirectional"))
      (node (ref "U$21") (pin "P$5") (pinfunction "P$5_P$5") (pintype "bidirectional"))
      (node (ref "U$22") (pin "P$5") (pinfunction "P$5_P$5") (pintype "bidirectional"))
      (node (ref "U$23") (pin "P$5") (pinfunction "P$5_P$5") (pintype "bidirectional"))
      (node (ref "U$24") (pin "P$5") (pinfunction "P$5_P$5") (pintype "bidirectional"))
      (node (ref "U$25") (pin "P$5") (pinfunction "P$5_P$5") (pintype "bidirectional"))
      (node (ref "U$26") (pin "P$5") (pinfunction "P$5_P$5") (pintype "bidirectional"))
      (node (ref "U$27") (pin "P$5") (pinfunction "P$5_P$5") (pintype "bidirectional"))
      (node (ref "U$3") (pin "P$5") (pinfunction "P$5_P$5") (pintype "bidirectional"))
      (node (ref "U$4") (pin "P$5") (pinfunction "P$5_P$5") (pintype "bidirectional"))
      (node (ref "U$5") (pin "P$5") (pinfunction "P$5_P$5") (pintype "bidirectional"))
      (node (ref "U$6") (pin "P$5") (pinfunction "P$5_P$5") (pintype "bidirectional"))
      (node (ref "U$7") (pin "P$5") (pinfunction "P$5_P$5") (pintype "bidirectional"))
      (node (ref "U$8") (pin "P$5") (pinfunction "P$5_P$5") (pintype "bidirectional"))
      (node (ref "U$9") (pin "P$5") (pinfunction "P$5_P$5") (pintype "bidirectional"))
    )
    (net (code "4") (name "Net-(J1-Pad6)") (class "Default")
      (node (ref "J1") (pin "6") (pinfunction "6_6") (pintype "passive"))
      (node (ref "U$1") (pin "P$4") (pinfunction "P$4_P$4") (pintype "bidirectional"))
      (node (ref "U$10") (pin "P$4") (pinfunction "P$4_P$4") (pintype "bidirectional"))
      (node (ref "U$17") (pin "P$4") (pinfunction "P$4_P$4") (pintype "bidirectional"))
      (node (ref "U$18") (pin "P$4") (pinfunction "P$4_P$4") (pintype "bidirectional"))
      (node (ref "U$19") (pin "P$4") (pinfunction "P$4_P$4") (pintype "bidirectional"))
      (node (ref "U$2") (pin "P$4") (pinfunction "P$4_P$4") (pintype "bidirectional"))
      (node (ref "U$20") (pin "P$4") (pinfunction "P$4_P$4") (pintype "bidirectional"))
      (node (ref "U$21") (pin "P$4") (pinfunction "P$4_P$4") (pintype "bidirectional"))
      (node (ref "U$22") (pin "P$4") (pinfunction "P$4_P$4") (pintype "bidirectional"))
      (node (ref "U$23") (pin "P$4") (pinfunction "P$4_P$4") (pintype "bidirectional"))
      (node (ref "U$24") (pin "P$4") (pinfunction "P$4_P$4") (pintype "bidirectional"))
      (node (ref "U$25") (pin "P$4") (pinfunction "P$4_P$4") (pintype "bidirectional"))
      (node (ref "U$26") (pin "P$4") (pinfunction "P$4_P$4") (pintype "bidirectional"))
      (node (ref "U$27") (pin "P$4") (pinfunction "P$4_P$4") (pintype "bidirectional"))
      (node (ref "U$3") (pin "P$4") (pinfunction "P$4_P$4") (pintype "bidirectional"))
      (node (ref "U$4") (pin "P$4") (pinfunction "P$4_P$4") (pintype "bidirectional"))
      (node (ref "U$5") (pin "P$4") (pinfunction "P$4_P$4") (pintype "bidirectional"))
      (node (ref "U$6") (pin "P$4") (pinfunction "P$4_P$4") (pintype "bidirectional"))
      (node (ref "U$7") (pin "P$4") (pinfunction "P$4_P$4") (pintype "bidirectional"))
      (node (ref "U$8") (pin "P$4") (pinfunction "P$4_P$4") (pintype "bidirectional"))
      (node (ref "U$9") (pin "P$4") (pinfunction "P$4_P$4") (pintype "bidirectional"))
    )
    (net (code "5") (name "Net-(R1-Pad2)") (class "Default")
      (node (ref "R1") (pin "2") (pinfunction "2_2") (pintype "passive"))
      (node (ref "U$27") (pin "P$1") (pinfunction "P$1_P$1") (pintype "bidirectional"))
    )
    (net (code "6") (name "Net-(R2-Pad2)") (class "Default")
      (node (ref "R2") (pin "2") (pinfunction "2_2") (pintype "passive"))
      (node (ref "U$27") (pin "P$2") (pinfunction "P$2_P$2") (pintype "bidirectional"))
    )
    (net (code "7") (name "Net-(R3-Pad2)") (class "Default")
      (node (ref "R3") (pin "2") (pinfunction "2_2") (pintype "passive"))
      (node (ref "U$27") (pin "P$3") (pinfunction "P$3_P$3") (pintype "bidirectional"))
    )
    (net (code "8") (name "Net-(R25-Pad2)") (class "Default")
      (node (ref "R25") (pin "2") (pinfunction "2_2") (pintype "passive"))
      (node (ref "U$26") (pin "P$3") (pinfunction "P$3_P$3") (pintype "bidirectional"))
    )
    (net (code "9") (name "Net-(R26-Pad2)") (class "Default")
      (node (ref "R26") (pin "2") (pinfunction "2_2") (pintype "passive"))
      (node (ref "U$26") (pin "P$2") (pinfunction "P$2_P$2") (pintype "bidirectional"))
    )
    (net (code "10") (name "Net-(R27-Pad2)") (class "Default")
      (node (ref "R27") (pin "2") (pinfunction "2_2") (pintype "passive"))
      (node (ref "U$26") (pin "P$1") (pinfunction "P$1_P$1") (pintype "bidirectional"))
    )
    (net (code "11") (name "Net-(R28-Pad2)") (class "Default")
      (node (ref "R28") (pin "2") (pinfunction "2_2") (pintype "passive"))
      (node (ref "U$25") (pin "P$3") (pinfunction "P$3_P$3") (pintype "bidirectional"))
    )
    (net (code "12") (name "Net-(R29-Pad2)") (class "Default")
      (node (ref "R29") (pin "2") (pinfunction "2_2") (pintype "passive"))
      (node (ref "U$25") (pin "P$2") (pinfunction "P$2_P$2") (pintype "bidirectional"))
    )
    (net (code "13") (name "Net-(R30-Pad2)") (class "Default")
      (node (ref "R30") (pin "2") (pinfunction "2_2") (pintype "passive"))
      (node (ref "U$25") (pin "P$1") (pinfunction "P$1_P$1") (pintype "bidirectional"))
    )
    (net (code "14") (name "Net-(R31-Pad2)") (class "Default")
      (node (ref "R31") (pin "2") (pinfunction "2_2") (pintype "passive"))
      (node (ref "U$24") (pin "P$3") (pinfunction "P$3_P$3") (pintype "bidirectional"))
    )
    (net (code "15") (name "Net-(R32-Pad2)") (class "Default")
      (node (ref "R32") (pin "2") (pinfunction "2_2") (pintype "passive"))
      (node (ref "U$24") (pin "P$2") (pinfunction "P$2_P$2") (pintype "bidirectional"))
    )
    (net (code "16") (name "Net-(R33-Pad2)") (class "Default")
      (node (ref "R33") (pin "2") (pinfunction "2_2") (pintype "passive"))
      (node (ref "U$24") (pin "P$1") (pinfunction "P$1_P$1") (pintype "bidirectional"))
    )
    (net (code "17") (name "Net-(R34-Pad2)") (class "Default")
      (node (ref "R34") (pin "2") (pinfunction "2_2") (pintype "passive"))
      (node (ref "U$23") (pin "P$3") (pinfunction "P$3_P$3") (pintype "bidirectional"))
    )
    (net (code "18") (name "Net-(R35-Pad2)") (class "Default")
      (node (ref "R35") (pin "2") (pinfunction "2_2") (pintype "passive"))
      (node (ref "U$23") (pin "P$2") (pinfunction "P$2_P$2") (pintype "bidirectional"))
    )
    (net (code "19") (name "Net-(R36-Pad2)") (class "Default")
      (node (ref "R36") (pin "2") (pinfunction "2_2") (pintype "passive"))
      (node (ref "U$23") (pin "P$1") (pinfunction "P$1_P$1") (pintype "bidirectional"))
    )
    (net (code "20") (name "Net-(R37-Pad2)") (class "Default")
      (node (ref "R37") (pin "2") (pinfunction "2_2") (pintype "passive"))
      (node (ref "U$22") (pin "P$3") (pinfunction "P$3_P$3") (pintype "bidirectional"))
    )
    (net (code "21") (name "Net-(R38-Pad2)") (class "Default")
      (node (ref "R38") (pin "2") (pinfunction "2_2") (pintype "passive"))
      (node (ref "U$22") (pin "P$2") (pinfunction "P$2_P$2") (pintype "bidirectional"))
    )
    (net (code "22") (name "Net-(R39-Pad2)") (class "Default")
      (node (ref "R39") (pin "2") (pinfunction "2_2") (pintype "passive"))
      (node (ref "U$22") (pin "P$1") (pinfunction "P$1_P$1") (pintype "bidirectional"))
    )
    (net (code "23") (name "Net-(R40-Pad2)") (class "Default")
      (node (ref "R40") (pin "2") (pinfunction "2_2") (pintype "passive"))
      (node (ref "U$21") (pin "P$3") (pinfunction "P$3_P$3") (pintype "bidirectional"))
    )
    (net (code "24") (name "Net-(R41-Pad2)") (class "Default")
      (node (ref "R41") (pin "2") (pinfunction "2_2") (pintype "passive"))
      (node (ref "U$21") (pin "P$2") (pinfunction "P$2_P$2") (pintype "bidirectional"))
    )
    (net (code "25") (name "Net-(R42-Pad2)") (class "Default")
      (node (ref "R42") (pin "2") (pinfunction "2_2") (pintype "passive"))
      (node (ref "U$21") (pin "P$1") (pinfunction "P$1_P$1") (pintype "bidirectional"))
    )
    (net (code "26") (name "Net-(R43-Pad2)") (class "Default")
      (node (ref "R43") (pin "2") (pinfunction "2_2") (pintype "passive"))
      (node (ref "U$20") (pin "P$3") (pinfunction "P$3_P$3") (pintype "bidirectional"))
    )
    (net (code "27") (name "Net-(R44-Pad2)") (class "Default")
      (node (ref "R44") (pin "2") (pinfunction "2_2") (pintype "passive"))
      (node (ref "U$20") (pin "P$2") (pinfunction "P$2_P$2") (pintype "bidirectional"))
    )
    (net (code "28") (name "Net-(R45-Pad2)") (class "Default")
      (node (ref "R45") (pin "2") (pinfunction "2_2") (pintype "passive"))
      (node (ref "U$20") (pin "P$1") (pinfunction "P$1_P$1") (pintype "bidirectional"))
    )
    (net (code "29") (name "Net-(R46-Pad2)") (class "Default")
      (node (ref "R46") (pin "2") (pinfunction "2_2") (pintype "passive"))
      (node (ref "U$19") (pin "P$3") (pinfunction "P$3_P$3") (pintype "bidirectional"))
    )
    (net (code "30") (name "Net-(R47-Pad2)") (class "Default")
      (node (ref "R47") (pin "2") (pinfunction "2_2") (pintype "passive"))
      (node (ref "U$19") (pin "P$2") (pinfunction "P$2_P$2") (pintype "bidirectional"))
    )
    (net (code "31") (name "Net-(R48-Pad2)") (class "Default")
      (node (ref "R48") (pin "2") (pinfunction "2_2") (pintype "passive"))
      (node (ref "U$19") (pin "P$1") (pinfunction "P$1_P$1") (pintype "bidirectional"))
    )
    (net (code "32") (name "Net-(R49-Pad2)") (class "Default")
      (node (ref "R49") (pin "2") (pinfunction "2_2") (pintype "passive"))
      (node (ref "U$18") (pin "P$3") (pinfunction "P$3_P$3") (pintype "bidirectional"))
    )
    (net (code "33") (name "Net-(R50-Pad2)") (class "Default")
      (node (ref "R50") (pin "2") (pinfunction "2_2") (pintype "passive"))
      (node (ref "U$18") (pin "P$2") (pinfunction "P$2_P$2") (pintype "bidirectional"))
    )
    (net (code "34") (name "Net-(R51-Pad2)") (class "Default")
      (node (ref "R51") (pin "2") (pinfunction "2_2") (pintype "passive"))
      (node (ref "U$18") (pin "P$1") (pinfunction "P$1_P$1") (pintype "bidirectional"))
    )
    (net (code "35") (name "Net-(R52-Pad2)") (class "Default")
      (node (ref "R52") (pin "2") (pinfunction "2_2") (pintype "passive"))
      (node (ref "U$17") (pin "P$3") (pinfunction "P$3_P$3") (pintype "bidirectional"))
    )
    (net (code "36") (name "Net-(R53-Pad2)") (class "Default")
      (node (ref "R53") (pin "2") (pinfunction "2_2") (pintype "passive"))
      (node (ref "U$17") (pin "P$2") (pinfunction "P$2_P$2") (pintype "bidirectional"))
    )
    (net (code "37") (name "Net-(R54-Pad2)") (class "Default")
      (node (ref "R54") (pin "2") (pinfunction "2_2") (pintype "passive"))
      (node (ref "U$17") (pin "P$1") (pinfunction "P$1_P$1") (pintype "bidirectional"))
    )
    (net (code "38") (name "Net-(R55-Pad2)") (class "Default")
      (node (ref "R55") (pin "2") (pinfunction "2_2") (pintype "passive"))
      (node (ref "U$1") (pin "P$3") (pinfunction "P$3_P$3") (pintype "bidirectional"))
    )
    (net (code "39") (name "Net-(R56-Pad2)") (class "Default")
      (node (ref "R56") (pin "2") (pinfunction "2_2") (pintype "passive"))
      (node (ref "U$1") (pin "P$2") (pinfunction "P$2_P$2") (pintype "bidirectional"))
    )
    (net (code "40") (name "Net-(R57-Pad2)") (class "Default")
      (node (ref "R57") (pin "2") (pinfunction "2_2") (pintype "passive"))
      (node (ref "U$1") (pin "P$1") (pinfunction "P$1_P$1") (pintype "bidirectional"))
    )
    (net (code "41") (name "Net-(R58-Pad2)") (class "Default")
      (node (ref "R58") (pin "2") (pinfunction "2_2") (pintype "passive"))
      (node (ref "U$2") (pin "P$3") (pinfunction "P$3_P$3") (pintype "bidirectional"))
    )
    (net (code "42") (name "Net-(R59-Pad2)") (class "Default")
      (node (ref "R59") (pin "2") (pinfunction "2_2") (pintype "passive"))
      (node (ref "U$2") (pin "P$2") (pinfunction "P$2_P$2") (pintype "bidirectional"))
    )
    (net (code "43") (name "Net-(R60-Pad2)") (class "Default")
      (node (ref "R60") (pin "2") (pinfunction "2_2") (pintype "passive"))
      (node (ref "U$2") (pin "P$1") (pinfunction "P$1_P$1") (pintype "bidirectional"))
    )
    (net (code "44") (name "Net-(R61-Pad2)") (class "Default")
      (node (ref "R61") (pin "2") (pinfunction "2_2") (pintype "passive"))
      (node (ref "U$3") (pin "P$3") (pinfunction "P$3_P$3") (pintype "bidirectional"))
    )
    (net (code "45") (name "Net-(R62-Pad2)") (class "Default")
      (node (ref "R62") (pin "2") (pinfunction "2_2") (pintype "passive"))
      (node (ref "U$3") (pin "P$2") (pinfunction "P$2_P$2") (pintype "bidirectional"))
    )
    (net (code "46") (name "Net-(R63-Pad2)") (class "Default")
      (node (ref "R63") (pin "2") (pinfunction "2_2") (pintype "passive"))
      (node (ref "U$3") (pin "P$1") (pinfunction "P$1_P$1") (pintype "bidirectional"))
    )
    (net (code "47") (name "Net-(R64-Pad2)") (class "Default")
      (node (ref "R64") (pin "2") (pinfunction "2_2") (pintype "passive"))
      (node (ref "U$4") (pin "P$3") (pinfunction "P$3_P$3") (pintype "bidirectional"))
    )
    (net (code "48") (name "Net-(R65-Pad2)") (class "Default")
      (node (ref "R65") (pin "2") (pinfunction "2_2") (pintype "passive"))
      (node (ref "U$4") (pin "P$2") (pinfunction "P$2_P$2") (pintype "bidirectional"))
    )
    (net (code "49") (name "Net-(R66-Pad2)") (class "Default")
      (node (ref "R66") (pin "2") (pinfunction "2_2") (pintype "passive"))
      (node (ref "U$4") (pin "P$1") (pinfunction "P$1_P$1") (pintype "bidirectional"))
    )
    (net (code "50") (name "Net-(R67-Pad2)") (class "Default")
      (node (ref "R67") (pin "2") (pinfunction "2_2") (pintype "passive"))
      (node (ref "U$5") (pin "P$3") (pinfunction "P$3_P$3") (pintype "bidirectional"))
    )
    (net (code "51") (name "Net-(R68-Pad2)") (class "Default")
      (node (ref "R68") (pin "2") (pinfunction "2_2") (pintype "passive"))
      (node (ref "U$5") (pin "P$2") (pinfunction "P$2_P$2") (pintype "bidirectional"))
    )
    (net (code "52") (name "Net-(R69-Pad2)") (class "Default")
      (node (ref "R69") (pin "2") (pinfunction "2_2") (pintype "passive"))
      (node (ref "U$5") (pin "P$1") (pinfunction "P$1_P$1") (pintype "bidirectional"))
    )
    (net (code "53") (name "Net-(R70-Pad2)") (class "Default")
      (node (ref "R70") (pin "2") (pinfunction "2_2") (pintype "passive"))
      (node (ref "U$6") (pin "P$3") (pinfunction "P$3_P$3") (pintype "bidirectional"))
    )
    (net (code "54") (name "Net-(R71-Pad2)") (class "Default")
      (node (ref "R71") (pin "2") (pinfunction "2_2") (pintype "passive"))
      (node (ref "U$6") (pin "P$2") (pinfunction "P$2_P$2") (pintype "bidirectional"))
    )
    (net (code "55") (name "Net-(R72-Pad2)") (class "Default")
      (node (ref "R72") (pin "2") (pinfunction "2_2") (pintype "passive"))
      (node (ref "U$6") (pin "P$1") (pinfunction "P$1_P$1") (pintype "bidirectional"))
    )
    (net (code "56") (name "Net-(R73-Pad2)") (class "Default")
      (node (ref "R73") (pin "2") (pinfunction "2_2") (pintype "passive"))
      (node (ref "U$7") (pin "P$3") (pinfunction "P$3_P$3") (pintype "bidirectional"))
    )
    (net (code "57") (name "Net-(R74-Pad2)") (class "Default")
      (node (ref "R74") (pin "2") (pinfunction "2_2") (pintype "passive"))
      (node (ref "U$7") (pin "P$2") (pinfunction "P$2_P$2") (pintype "bidirectional"))
    )
    (net (code "58") (name "Net-(R75-Pad2)") (class "Default")
      (node (ref "R75") (pin "2") (pinfunction "2_2") (pintype "passive"))
      (node (ref "U$7") (pin "P$1") (pinfunction "P$1_P$1") (pintype "bidirectional"))
    )
    (net (code "59") (name "Net-(R76-Pad2)") (class "Default")
      (node (ref "R76") (pin "2") (pinfunction "2_2") (pintype "passive"))
      (node (ref "U$8") (pin "P$3") (pinfunction "P$3_P$3") (pintype "bidirectional"))
    )
    (net (code "60") (name "Net-(R77-Pad2)") (class "Default")
      (node (ref "R77") (pin "2") (pinfunction "2_2") (pintype "passive"))
      (node (ref "U$8") (pin "P$2") (pinfunction "P$2_P$2") (pintype "bidirectional"))
    )
    (net (code "61") (name "Net-(R78-Pad2)") (class "Default")
      (node (ref "R78") (pin "2") (pinfunction "2_2") (pintype "passive"))
      (node (ref "U$8") (pin "P$1") (pinfunction "P$1_P$1") (pintype "bidirectional"))
    )
    (net (code "62") (name "Net-(R79-Pad2)") (class "Default")
      (node (ref "R79") (pin "2") (pinfunction "2_2") (pintype "passive"))
      (node (ref "U$9") (pin "P$3") (pinfunction "P$3_P$3") (pintype "bidirectional"))
    )
    (net (code "63") (name "Net-(R80-Pad2)") (class "Default")
      (node (ref "R80") (pin "2") (pinfunction "2_2") (pintype "passive"))
      (node (ref "U$9") (pin "P$2") (pinfunction "P$2_P$2") (pintype "bidirectional"))
    )
    (net (code "64") (name "Net-(R81-Pad2)") (class "Default")
      (node (ref "R81") (pin "2") (pinfunction "2_2") (pintype "passive"))
      (node (ref "U$9") (pin "P$1") (pinfunction "P$1_P$1") (pintype "bidirectional"))
    )
    (net (code "65") (name "Net-(R82-Pad2)") (class "Default")
      (node (ref "R82") (pin "2") (pinfunction "2_2") (pintype "passive"))
      (node (ref "U$10") (pin "P$3") (pinfunction "P$3_P$3") (pintype "bidirectional"))
    )
    (net (code "66") (name "Net-(R83-Pad2)") (class "Default")
      (node (ref "R83") (pin "2") (pinfunction "2_2") (pintype "passive"))
      (node (ref "U$10") (pin "P$2") (pinfunction "P$2_P$2") (pintype "bidirectional"))
    )
    (net (code "67") (name "Net-(R84-Pad2)") (class "Default")
      (node (ref "R84") (pin "2") (pinfunction "2_2") (pintype "passive"))
      (node (ref "U$10") (pin "P$1") (pinfunction "P$1_P$1") (pintype "bidirectional"))
    )
    (net (code "68") (name "Net-(R85-Pad1)") (class "Default")
      (node (ref "R85") (pin "1") (pinfunction "1_1") (pintype "passive"))
      (node (ref "U$49") (pin "P$3") (pinfunction "P$3_P$3") (pintype "bidirectional"))
    )
    (net (code "69") (name "Net-(R86-Pad1)") (class "Default")
      (node (ref "R86") (pin "1") (pinfunction "1_1") (pintype "passive"))
      (node (ref "U$49") (pin "P$2") (pinfunction "P$2_P$2") (pintype "bidirectional"))
    )
    (net (code "70") (name "Net-(R87-Pad1)") (class "Default")
      (node (ref "R87") (pin "1") (pinfunction "1_1") (pintype "passive"))
      (node (ref "U$49") (pin "P$1") (pinfunction "P$1_P$1") (pintype "bidirectional"))
    )
    (net (code "71") (name "Net-(R88-Pad1)") (class "Default")
      (node (ref "R88") (pin "1") (pinfunction "1_1") (pintype "passive"))
      (node (ref "U$48") (pin "P$3") (pinfunction "P$3_P$3") (pintype "bidirectional"))
    )
    (net (code "72") (name "Net-(R89-Pad1)") (class "Default")
      (node (ref "R89") (pin "1") (pinfunction "1_1") (pintype "passive"))
      (node (ref "U$48") (pin "P$2") (pinfunction "P$2_P$2") (pintype "bidirectional"))
    )
    (net (code "73") (name "Net-(R90-Pad1)") (class "Default")
      (node (ref "R90") (pin "1") (pinfunction "1_1") (pintype "passive"))
      (node (ref "U$48") (pin "P$1") (pinfunction "P$1_P$1") (pintype "bidirectional"))
    )
    (net (code "74") (name "Net-(R91-Pad1)") (class "Default")
      (node (ref "R91") (pin "1") (pinfunction "1_1") (pintype "passive"))
      (node (ref "U$47") (pin "P$3") (pinfunction "P$3_P$3") (pintype "bidirectional"))
    )
    (net (code "75") (name "Net-(R92-Pad1)") (class "Default")
      (node (ref "R92") (pin "1") (pinfunction "1_1") (pintype "passive"))
      (node (ref "U$47") (pin "P$2") (pinfunction "P$2_P$2") (pintype "bidirectional"))
    )
    (net (code "76") (name "Net-(R93-Pad1)") (class "Default")
      (node (ref "R93") (pin "1") (pinfunction "1_1") (pintype "passive"))
      (node (ref "U$47") (pin "P$1") (pinfunction "P$1_P$1") (pintype "bidirectional"))
    )
    (net (code "77") (name "Net-(R94-Pad1)") (class "Default")
      (node (ref "R94") (pin "1") (pinfunction "1_1") (pintype "passive"))
      (node (ref "U$16") (pin "P$3") (pinfunction "P$3_P$3") (pintype "bidirectional"))
    )
    (net (code "78") (name "Net-(R95-Pad1)") (class "Default")
      (node (ref "R95") (pin "1") (pinfunction "1_1") (pintype "passive"))
      (node (ref "U$16") (pin "P$2") (pinfunction "P$2_P$2") (pintype "bidirectional"))
    )
    (net (code "79") (name "Net-(R96-Pad1)") (class "Default")
      (node (ref "R96") (pin "1") (pinfunction "1_1") (pintype "passive"))
      (node (ref "U$16") (pin "P$1") (pinfunction "P$1_P$1") (pintype "bidirectional"))
    )
    (net (code "80") (name "Net-(R97-Pad1)") (class "Default")
      (node (ref "R97") (pin "1") (pinfunction "1_1") (pintype "passive"))
      (node (ref "U$15") (pin "P$3") (pinfunction "P$3_P$3") (pintype "bidirectional"))
    )
    (net (code "81") (name "Net-(R98-Pad1)") (class "Default")
      (node (ref "R98") (pin "1") (pinfunction "1_1") (pintype "passive"))
      (node (ref "U$15") (pin "P$2") (pinfunction "P$2_P$2") (pintype "bidirectional"))
    )
    (net (code "82") (name "Net-(R99-Pad1)") (class "Default")
      (node (ref "R99") (pin "1") (pinfunction "1_1") (pintype "passive"))
      (node (ref "U$15") (pin "P$1") (pinfunction "P$1_P$1") (pintype "bidirectional"))
    )
    (net (code "83") (name "Net-(R100-Pad1)") (class "Default")
      (node (ref "R100") (pin "1") (pinfunction "1_1") (pintype "passive"))
      (node (ref "U$14") (pin "P$3") (pinfunction "P$3_P$3") (pintype "bidirectional"))
    )
    (net (code "84") (name "Net-(R101-Pad1)") (class "Default")
      (node (ref "R101") (pin "1") (pinfunction "1_1") (pintype "passive"))
      (node (ref "U$14") (pin "P$2") (pinfunction "P$2_P$2") (pintype "bidirectional"))
    )
    (net (code "85") (name "Net-(R102-Pad1)") (class "Default")
      (node (ref "R102") (pin "1") (pinfunction "1_1") (pintype "passive"))
      (node (ref "U$14") (pin "P$1") (pinfunction "P$1_P$1") (pintype "bidirectional"))
    )
    (net (code "86") (name "Net-(R103-Pad1)") (class "Default")
      (node (ref "R103") (pin "1") (pinfunction "1_1") (pintype "passive"))
      (node (ref "U$13") (pin "P$3") (pinfunction "P$3_P$3") (pintype "bidirectional"))
    )
    (net (code "87") (name "Net-(R104-Pad1)") (class "Default")
      (node (ref "R104") (pin "1") (pinfunction "1_1") (pintype "passive"))
      (node (ref "U$13") (pin "P$2") (pinfunction "P$2_P$2") (pintype "bidirectional"))
    )
    (net (code "88") (name "Net-(R105-Pad1)") (class "Default")
      (node (ref "R105") (pin "1") (pinfunction "1_1") (pintype "passive"))
      (node (ref "U$13") (pin "P$1") (pinfunction "P$1_P$1") (pintype "bidirectional"))
    )
    (net (code "89") (name "Net-(R106-Pad1)") (class "Default")
      (node (ref "R106") (pin "1") (pinfunction "1_1") (pintype "passive"))
      (node (ref "U$12") (pin "P$3") (pinfunction "P$3_P$3") (pintype "bidirectional"))
    )
    (net (code "90") (name "Net-(R107-Pad1)") (class "Default")
      (node (ref "R107") (pin "1") (pinfunction "1_1") (pintype "passive"))
      (node (ref "U$12") (pin "P$2") (pinfunction "P$2_P$2") (pintype "bidirectional"))
    )
    (net (code "91") (name "Net-(R108-Pad1)") (class "Default")
      (node (ref "R108") (pin "1") (pinfunction "1_1") (pintype "passive"))
      (node (ref "U$12") (pin "P$1") (pinfunction "P$1_P$1") (pintype "bidirectional"))
    )
    (net (code "92") (name "Net-(R109-Pad1)") (class "Default")
      (node (ref "R109") (pin "1") (pinfunction "1_1") (pintype "passive"))
      (node (ref "U$11") (pin "P$3") (pinfunction "P$3_P$3") (pintype "bidirectional"))
    )
    (net (code "93") (name "Net-(R110-Pad1)") (class "Default")
      (node (ref "R110") (pin "1") (pinfunction "1_1") (pintype "passive"))
      (node (ref "U$11") (pin "P$2") (pinfunction "P$2_P$2") (pintype "bidirectional"))
    )
    (net (code "94") (name "Net-(R111-Pad1)") (class "Default")
      (node (ref "R111") (pin "1") (pinfunction "1_1") (pintype "passive"))
      (node (ref "U$11") (pin "P$1") (pinfunction "P$1_P$1") (pintype "bidirectional"))
    )
    (net (code "95") (name "Net-(R112-Pad1)") (class "Default")
      (node (ref "R112") (pin "1") (pinfunction "1_1") (pintype "passive"))
      (node (ref "U$57") (pin "P$1") (pinfunction "P$1_P$1") (pintype "bidirectional"))
    )
    (net (code "96") (name "Net-(R113-Pad1)") (class "Default")
      (node (ref "R113") (pin "1") (pinfunction "1_1") (pintype "passive"))
      (node (ref "U$57") (pin "P$2") (pinfunction "P$2_P$2") (pintype "bidirectional"))
    )
    (net (code "97") (name "Net-(R114-Pad1)") (class "Default")
      (node (ref "R114") (pin "1") (pinfunction "1_1") (pintype "passive"))
      (node (ref "U$57") (pin "P$3") (pinfunction "P$3_P$3") (pintype "bidirectional"))
    )
    (net (code "98") (name "Net-(R115-Pad1)") (class "Default")
      (node (ref "R115") (pin "1") (pinfunction "1_1") (pintype "passive"))
      (node (ref "U$56") (pin "P$1") (pinfunction "P$1_P$1") (pintype "bidirectional"))
    )
    (net (code "99") (name "Net-(R116-Pad1)") (class "Default")
      (node (ref "R116") (pin "1") (pinfunction "1_1") (pintype "passive"))
      (node (ref "U$56") (pin "P$2") (pinfunction "P$2_P$2") (pintype "bidirectional"))
    )
    (net (code "100") (name "Net-(R117-Pad1)") (class "Default")
      (node (ref "R117") (pin "1") (pinfunction "1_1") (pintype "passive"))
      (node (ref "U$56") (pin "P$3") (pinfunction "P$3_P$3") (pintype "bidirectional"))
    )
    (net (code "101") (name "Net-(R118-Pad1)") (class "Default")
      (node (ref "R118") (pin "1") (pinfunction "1_1") (pintype "passive"))
      (node (ref "U$55") (pin "P$1") (pinfunction "P$1_P$1") (pintype "bidirectional"))
    )
    (net (code "102") (name "Net-(R119-Pad1)") (class "Default")
      (node (ref "R119") (pin "1") (pinfunction "1_1") (pintype "passive"))
      (node (ref "U$55") (pin "P$2") (pinfunction "P$2_P$2") (pintype "bidirectional"))
    )
    (net (code "103") (name "Net-(R120-Pad1)") (class "Default")
      (node (ref "R120") (pin "1") (pinfunction "1_1") (pintype "passive"))
      (node (ref "U$55") (pin "P$3") (pinfunction "P$3_P$3") (pintype "bidirectional"))
    )
    (net (code "104") (name "Net-(R121-Pad1)") (class "Default")
      (node (ref "R121") (pin "1") (pinfunction "1_1") (pintype "passive"))
      (node (ref "U$54") (pin "P$1") (pinfunction "P$1_P$1") (pintype "bidirectional"))
    )
    (net (code "105") (name "Net-(R122-Pad1)") (class "Default")
      (node (ref "R122") (pin "1") (pinfunction "1_1") (pintype "passive"))
      (node (ref "U$54") (pin "P$3") (pinfunction "P$3_P$3") (pintype "bidirectional"))
    )
    (net (code "106") (name "Net-(R123-Pad1)") (class "Default")
      (node (ref "R123") (pin "1") (pinfunction "1_1") (pintype "passive"))
      (node (ref "U$54") (pin "P$2") (pinfunction "P$2_P$2") (pintype "bidirectional"))
    )
    (net (code "107") (name "Net-(R124-Pad1)") (class "Default")
      (node (ref "R124") (pin "1") (pinfunction "1_1") (pintype "passive"))
      (node (ref "U$53") (pin "P$1") (pinfunction "P$1_P$1") (pintype "bidirectional"))
    )
    (net (code "108") (name "Net-(R125-Pad1)") (class "Default")
      (node (ref "R125") (pin "1") (pinfunction "1_1") (pintype "passive"))
      (node (ref "U$53") (pin "P$2") (pinfunction "P$2_P$2") (pintype "bidirectional"))
    )
    (net (code "109") (name "Net-(R126-Pad1)") (class "Default")
      (node (ref "R126") (pin "1") (pinfunction "1_1") (pintype "passive"))
      (node (ref "U$53") (pin "P$3") (pinfunction "P$3_P$3") (pintype "bidirectional"))
    )
    (net (code "110") (name "Net-(R127-Pad1)") (class "Default")
      (node (ref "R127") (pin "1") (pinfunction "1_1") (pintype "passive"))
      (node (ref "U$52") (pin "P$1") (pinfunction "P$1_P$1") (pintype "bidirectional"))
    )
    (net (code "111") (name "Net-(R128-Pad1)") (class "Default")
      (node (ref "R128") (pin "1") (pinfunction "1_1") (pintype "passive"))
      (node (ref "U$52") (pin "P$2") (pinfunction "P$2_P$2") (pintype "bidirectional"))
    )
    (net (code "112") (name "Net-(R129-Pad1)") (class "Default")
      (node (ref "R129") (pin "1") (pinfunction "1_1") (pintype "passive"))
      (node (ref "U$52") (pin "P$3") (pinfunction "P$3_P$3") (pintype "bidirectional"))
    )
    (net (code "113") (name "Net-(R130-Pad1)") (class "Default")
      (node (ref "R130") (pin "1") (pinfunction "1_1") (pintype "passive"))
      (node (ref "U$51") (pin "P$1") (pinfunction "P$1_P$1") (pintype "bidirectional"))
    )
    (net (code "114") (name "Net-(R131-Pad1)") (class "Default")
      (node (ref "R131") (pin "1") (pinfunction "1_1") (pintype "passive"))
      (node (ref "U$51") (pin "P$2") (pinfunction "P$2_P$2") (pintype "bidirectional"))
    )
    (net (code "115") (name "Net-(R132-Pad1)") (class "Default")
      (node (ref "R132") (pin "1") (pinfunction "1_1") (pintype "passive"))
      (node (ref "U$51") (pin "P$3") (pinfunction "P$3_P$3") (pintype "bidirectional"))
    )
    (net (code "116") (name "Net-(R133-Pad1)") (class "Default")
      (node (ref "R133") (pin "1") (pinfunction "1_1") (pintype "passive"))
      (node (ref "U$50") (pin "P$1") (pinfunction "P$1_P$1") (pintype "bidirectional"))
    )
    (net (code "117") (name "Net-(R134-Pad1)") (class "Default")
      (node (ref "R134") (pin "1") (pinfunction "1_1") (pintype "passive"))
      (node (ref "U$50") (pin "P$2") (pinfunction "P$2_P$2") (pintype "bidirectional"))
    )
    (net (code "118") (name "Net-(R135-Pad1)") (class "Default")
      (node (ref "R135") (pin "1") (pinfunction "1_1") (pintype "passive"))
      (node (ref "U$50") (pin "P$3") (pinfunction "P$3_P$3") (pintype "bidirectional"))
    )
    (net (code "119") (name "Net-(R136-Pad1)") (class "Default")
      (node (ref "R136") (pin "1") (pinfunction "1_1") (pintype "passive"))
      (node (ref "U$38") (pin "P$1") (pinfunction "P$1_P$1") (pintype "bidirectional"))
    )
    (net (code "120") (name "Net-(R137-Pad1)") (class "Default")
      (node (ref "R137") (pin "1") (pinfunction "1_1") (pintype "passive"))
      (node (ref "U$38") (pin "P$2") (pinfunction "P$2_P$2") (pintype "bidirectional"))
    )
    (net (code "121") (name "Net-(R138-Pad1)") (class "Default")
      (node (ref "R138") (pin "1") (pinfunction "1_1") (pintype "passive"))
      (node (ref "U$38") (pin "P$3") (pinfunction "P$3_P$3") (pintype "bidirectional"))
    )
    (net (code "122") (name "Net-(R139-Pad1)") (class "Default")
      (node (ref "R139") (pin "1") (pinfunction "1_1") (pintype "passive"))
      (node (ref "U$37") (pin "P$1") (pinfunction "P$1_P$1") (pintype "bidirectional"))
    )
    (net (code "123") (name "Net-(R140-Pad1)") (class "Default")
      (node (ref "R140") (pin "1") (pinfunction "1_1") (pintype "passive"))
      (node (ref "U$37") (pin "P$2") (pinfunction "P$2_P$2") (pintype "bidirectional"))
    )
    (net (code "124") (name "Net-(R141-Pad1)") (class "Default")
      (node (ref "R141") (pin "1") (pinfunction "1_1") (pintype "passive"))
      (node (ref "U$37") (pin "P$3") (pinfunction "P$3_P$3") (pintype "bidirectional"))
    )
    (net (code "125") (name "Net-(R142-Pad1)") (class "Default")
      (node (ref "R142") (pin "1") (pinfunction "1_1") (pintype "passive"))
      (node (ref "U$36") (pin "P$1") (pinfunction "P$1_P$1") (pintype "bidirectional"))
    )
    (net (code "126") (name "Net-(R143-Pad1)") (class "Default")
      (node (ref "R143") (pin "1") (pinfunction "1_1") (pintype "passive"))
      (node (ref "U$36") (pin "P$3") (pinfunction "P$3_P$3") (pintype "bidirectional"))
    )
    (net (code "127") (name "Net-(R144-Pad1)") (class "Default")
      (node (ref "R144") (pin "1") (pinfunction "1_1") (pintype "passive"))
      (node (ref "U$36") (pin "P$2") (pinfunction "P$2_P$2") (pintype "bidirectional"))
    )
    (net (code "128") (name "Net-(R145-Pad1)") (class "Default")
      (node (ref "R145") (pin "1") (pinfunction "1_1") (pintype "passive"))
      (node (ref "U$35") (pin "P$1") (pinfunction "P$1_P$1") (pintype "bidirectional"))
    )
    (net (code "129") (name "Net-(R146-Pad1)") (class "Default")
      (node (ref "R146") (pin "1") (pinfunction "1_1") (pintype "passive"))
      (node (ref "U$35") (pin "P$2") (pinfunction "P$2_P$2") (pintype "bidirectional"))
    )
    (net (code "130") (name "Net-(R147-Pad1)") (class "Default")
      (node (ref "R147") (pin "1") (pinfunction "1_1") (pintype "passive"))
      (node (ref "U$35") (pin "P$3") (pinfunction "P$3_P$3") (pintype "bidirectional"))
    )
    (net (code "131") (name "VCC") (class "Default")
      (node (ref "J1") (pin "1") (pinfunction "1_1") (pintype "passive"))
      (node (ref "J1") (pin "2") (pinfunction "2_2") (pintype "passive"))
      (node (ref "R1") (pin "1") (pinfunction "1_1") (pintype "passive"))
      (node (ref "R100") (pin "2") (pinfunction "2_2") (pintype "passive"))
      (node (ref "R101") (pin "2") (pinfunction "2_2") (pintype "passive"))
      (node (ref "R102") (pin "2") (pinfunction "2_2") (pintype "passive"))
      (node (ref "R103") (pin "2") (pinfunction "2_2") (pintype "passive"))
      (node (ref "R104") (pin "2") (pinfunction "2_2") (pintype "passive"))
      (node (ref "R105") (pin "2") (pinfunction "2_2") (pintype "passive"))
      (node (ref "R106") (pin "2") (pinfunction "2_2") (pintype "passive"))
      (node (ref "R107") (pin "2") (pinfunction "2_2") (pintype "passive"))
      (node (ref "R108") (pin "2") (pinfunction "2_2") (pintype "passive"))
      (node (ref "R109") (pin "2") (pinfunction "2_2") (pintype "passive"))
      (node (ref "R110") (pin "2") (pinfunction "2_2") (pintype "passive"))
      (node (ref "R111") (pin "2") (pinfunction "2_2") (pintype "passive"))
      (node (ref "R112") (pin "2") (pinfunction "2_2") (pintype "passive"))
      (node (ref "R113") (pin "2") (pinfunction "2_2") (pintype "passive"))
      (node (ref "R114") (pin "2") (pinfunction "2_2") (pintype "passive"))
      (node (ref "R115") (pin "2") (pinfunction "2_2") (pintype "passive"))
      (node (ref "R116") (pin "2") (pinfunction "2_2") (pintype "passive"))
      (node (ref "R117") (pin "2") (pinfunction "2_2") (pintype "passive"))
      (node (ref "R118") (pin "2") (pinfunction "2_2") (pintype "passive"))
      (node (ref "R119") (pin "2") (pinfunction "2_2") (pintype "passive"))
      (node (ref "R120") (pin "2") (pinfunction "2_2") (pintype "passive"))
      (node (ref "R121") (pin "2") (pinfunction "2_2") (pintype "passive"))
      (node (ref "R122") (pin "2") (pinfunction "2_2") (pintype "passive"))
      (node (ref "R123") (pin "2") (pinfunction "2_2") (pintype "passive"))
      (node (ref "R124") (pin "2") (pinfunction "2_2") (pintype "passive"))
      (node (ref "R125") (pin "2") (pinfunction "2_2") (pintype "passive"))
      (node (ref "R126") (pin "2") (pinfunction "2_2") (pintype "passive"))
      (node (ref "R127") (pin "2") (pinfunction "2_2") (pintype "passive"))
      (node (ref "R128") (pin "2") (pinfunction "2_2") (pintype "passive"))
      (node (ref "R129") (pin "2") (pinfunction "2_2") (pintype "passive"))
      (node (ref "R130") (pin "2") (pinfunction "2_2") (pintype "passive"))
      (node (ref "R131") (pin "2") (pinfunction "2_2") (pintype "passive"))
      (node (ref "R132") (pin "2") (pinfunction "2_2") (pintype "passive"))
      (node (ref "R133") (pin "2") (pinfunction "2_2") (pintype "passive"))
      (node (ref "R134") (pin "2") (pinfunction "2_2") (pintype "passive"))
      (node (ref "R135") (pin "2") (pinfunction "2_2") (pintype "passive"))
      (node (ref "R136") (pin "2") (pinfunction "2_2") (pintype "passive"))
      (node (ref "R137") (pin "2") (pinfunction "2_2") (pintype "passive"))
      (node (ref "R138") (pin "2") (pinfunction "2_2") (pintype "passive"))
      (node (ref "R139") (pin "2") (pinfunction "2_2") (pintype "passive"))
      (node (ref "R140") (pin "2") (pinfunction "2_2") (pintype "passive"))
      (node (ref "R141") (pin "2") (pinfunction "2_2") (pintype "passive"))
      (node (ref "R142") (pin "2") (pinfunction "2_2") (pintype "passive"))
      (node (ref "R143") (pin "2") (pinfunction "2_2") (pintype "passive"))
      (node (ref "R144") (pin "2") (pinfunction "2_2") (pintype "passive"))
      (node (ref "R145") (pin "2") (pinfunction "2_2") (pintype "passive"))
      (node (ref "R146") (pin "2") (pinfunction "2_2") (pintype "passive"))
      (node (ref "R147") (pin "2") (pinfunction "2_2") (pintype "passive"))
      (node (ref "R2") (pin "1") (pinfunction "1_1") (pintype "passive"))
      (node (ref "R25") (pin "1") (pinfunction "1_1") (pintype "passive"))
      (node (ref "R26") (pin "1") (pinfunction "1_1") (pintype "passive"))
      (node (ref "R27") (pin "1") (pinfunction "1_1") (pintype "passive"))
      (node (ref "R28") (pin "1") (pinfunction "1_1") (pintype "passive"))
      (node (ref "R29") (pin "1") (pinfunction "1_1") (pintype "passive"))
      (node (ref "R3") (pin "1") (pinfunction "1_1") (pintype "passive"))
      (node (ref "R30") (pin "1") (pinfunction "1_1") (pintype "passive"))
      (node (ref "R31") (pin "1") (pinfunction "1_1") (pintype "passive"))
      (node (ref "R32") (pin "1") (pinfunction "1_1") (pintype "passive"))
      (node (ref "R33") (pin "1") (pinfunction "1_1") (pintype "passive"))
      (node (ref "R34") (pin "1") (pinfunction "1_1") (pintype "passive"))
      (node (ref "R35") (pin "1") (pinfunction "1_1") (pintype "passive"))
      (node (ref "R36") (pin "1") (pinfunction "1_1") (pintype "passive"))
      (node (ref "R37") (pin "1") (pinfunction "1_1") (pintype "passive"))
      (node (ref "R38") (pin "1") (pinfunction "1_1") (pintype "passive"))
      (node (ref "R39") (pin "1") (pinfunction "1_1") (pintype "passive"))
      (node (ref "R40") (pin "1") (pinfunction "1_1") (pintype "passive"))
      (node (ref "R41") (pin "1") (pinfunction "1_1") (pintype "passive"))
      (node (ref "R42") (pin "1") (pinfunction "1_1") (pintype "passive"))
      (node (ref "R43") (pin "1") (pinfunction "1_1") (pintype "passive"))
      (node (ref "R44") (pin "1") (pinfunction "1_1") (pintype "passive"))
      (node (ref "R45") (pin "1") (pinfunction "1_1") (pintype "passive"))
      (node (ref "R46") (pin "1") (pinfunction "1_1") (pintype "passive"))
      (node (ref "R47") (pin "1") (pinfunction "1_1") (pintype "passive"))
      (node (ref "R48") (pin "1") (pinfunction "1_1") (pintype "passive"))
      (node (ref "R49") (pin "1") (pinfunction "1_1") (pintype "passive"))
      (node (ref "R50") (pin "1") (pinfunction "1_1") (pintype "passive"))
      (node (ref "R51") (pin "1") (pinfunction "1_1") (pintype "passive"))
      (node (ref "R52") (pin "1") (pinfunction "1_1") (pintype "passive"))
      (node (ref "R53") (pin "1") (pinfunction "1_1") (pintype "passive"))
      (node (ref "R54") (pin "1") (pinfunction "1_1") (pintype "passive"))
      (node (ref "R55") (pin "1") (pinfunction "1_1") (pintype "passive"))
      (node (ref "R56") (pin "1") (pinfunction "1_1") (pintype "passive"))
      (node (ref "R57") (pin "1") (pinfunction "1_1") (pintype "passive"))
      (node (ref "R58") (pin "1") (pinfunction "1_1") (pintype "passive"))
      (node (ref "R59") (pin "1") (pinfunction "1_1") (pintype "passive"))
      (node (ref "R60") (pin "1") (pinfunction "1_1") (pintype "passive"))
      (node (ref "R61") (pin "1") (pinfunction "1_1") (pintype "passive"))
      (node (ref "R62") (pin "1") (pinfunction "1_1") (pintype "passive"))
      (node (ref "R63") (pin "1") (pinfunction "1_1") (pintype "passive"))
      (node (ref "R64") (pin "1") (pinfunction "1_1") (pintype "passive"))
      (node (ref "R65") (pin "1") (pinfunction "1_1") (pintype "passive"))
      (node (ref "R66") (pin "1") (pinfunction "1_1") (pintype "passive"))
      (node (ref "R67") (pin "1") (pinfunction "1_1") (pintype "passive"))
      (node (ref "R68") (pin "1") (pinfunction "1_1") (pintype "passive"))
      (node (ref "R69") (pin "1") (pinfunction "1_1") (pintype "passive"))
      (node (ref "R70") (pin "1") (pinfunction "1_1") (pintype "passive"))
      (node (ref "R71") (pin "1") (pinfunction "1_1") (pintype "passive"))
      (node (ref "R72") (pin "1") (pinfunction "1_1") (pintype "passive"))
      (node (ref "R73") (pin "1") (pinfunction "1_1") (pintype "passive"))
      (node (ref "R74") (pin "1") (pinfunction "1_1") (pintype "passive"))
      (node (ref "R75") (pin "1") (pinfunction "1_1") (pintype "passive"))
      (node (ref "R76") (pin "1") (pinfunction "1_1") (pintype "passive"))
      (node (ref "R77") (pin "1") (pinfunction "1_1") (pintype "passive"))
      (node (ref "R78") (pin "1") (pinfunction "1_1") (pintype "passive"))
      (node (ref "R79") (pin "1") (pinfunction "1_1") (pintype "passive"))
      (node (ref "R80") (pin "1") (pinfunction "1_1") (pintype "passive"))
      (node (ref "R81") (pin "1") (pinfunction "1_1") (pintype "passive"))
      (node (ref "R82") (pin "1") (pinfunction "1_1") (pintype "passive"))
      (node (ref "R83") (pin "1") (pinfunction "1_1") (pintype "passive"))
      (node (ref "R84") (pin "1") (pinfunction "1_1") (pintype "passive"))
      (node (ref "R85") (pin "2") (pinfunction "2_2") (pintype "passive"))
      (node (ref "R86") (pin "2") (pinfunction "2_2") (pintype "passive"))
      (node (ref "R87") (pin "2") (pinfunction "2_2") (pintype "passive"))
      (node (ref "R88") (pin "2") (pinfunction "2_2") (pintype "passive"))
      (node (ref "R89") (pin "2") (pinfunction "2_2") (pintype "passive"))
      (node (ref "R90") (pin "2") (pinfunction "2_2") (pintype "passive"))
      (node (ref "R91") (pin "2") (pinfunction "2_2") (pintype "passive"))
      (node (ref "R92") (pin "2") (pinfunction "2_2") (pintype "passive"))
      (node (ref "R93") (pin "2") (pinfunction "2_2") (pintype "passive"))
      (node (ref "R94") (pin "2") (pinfunction "2_2") (pintype "passive"))
      (node (ref "R95") (pin "2") (pinfunction "2_2") (pintype "passive"))
      (node (ref "R96") (pin "2") (pinfunction "2_2") (pintype "passive"))
      (node (ref "R97") (pin "2") (pinfunction "2_2") (pintype "passive"))
      (node (ref "R98") (pin "2") (pinfunction "2_2") (pintype "passive"))
      (node (ref "R99") (pin "2") (pinfunction "2_2") (pintype "passive"))
    )
  )
)
